# w65c265sxb_ym2149.net
KiCad netlist of a schematic drawn in EAGLE
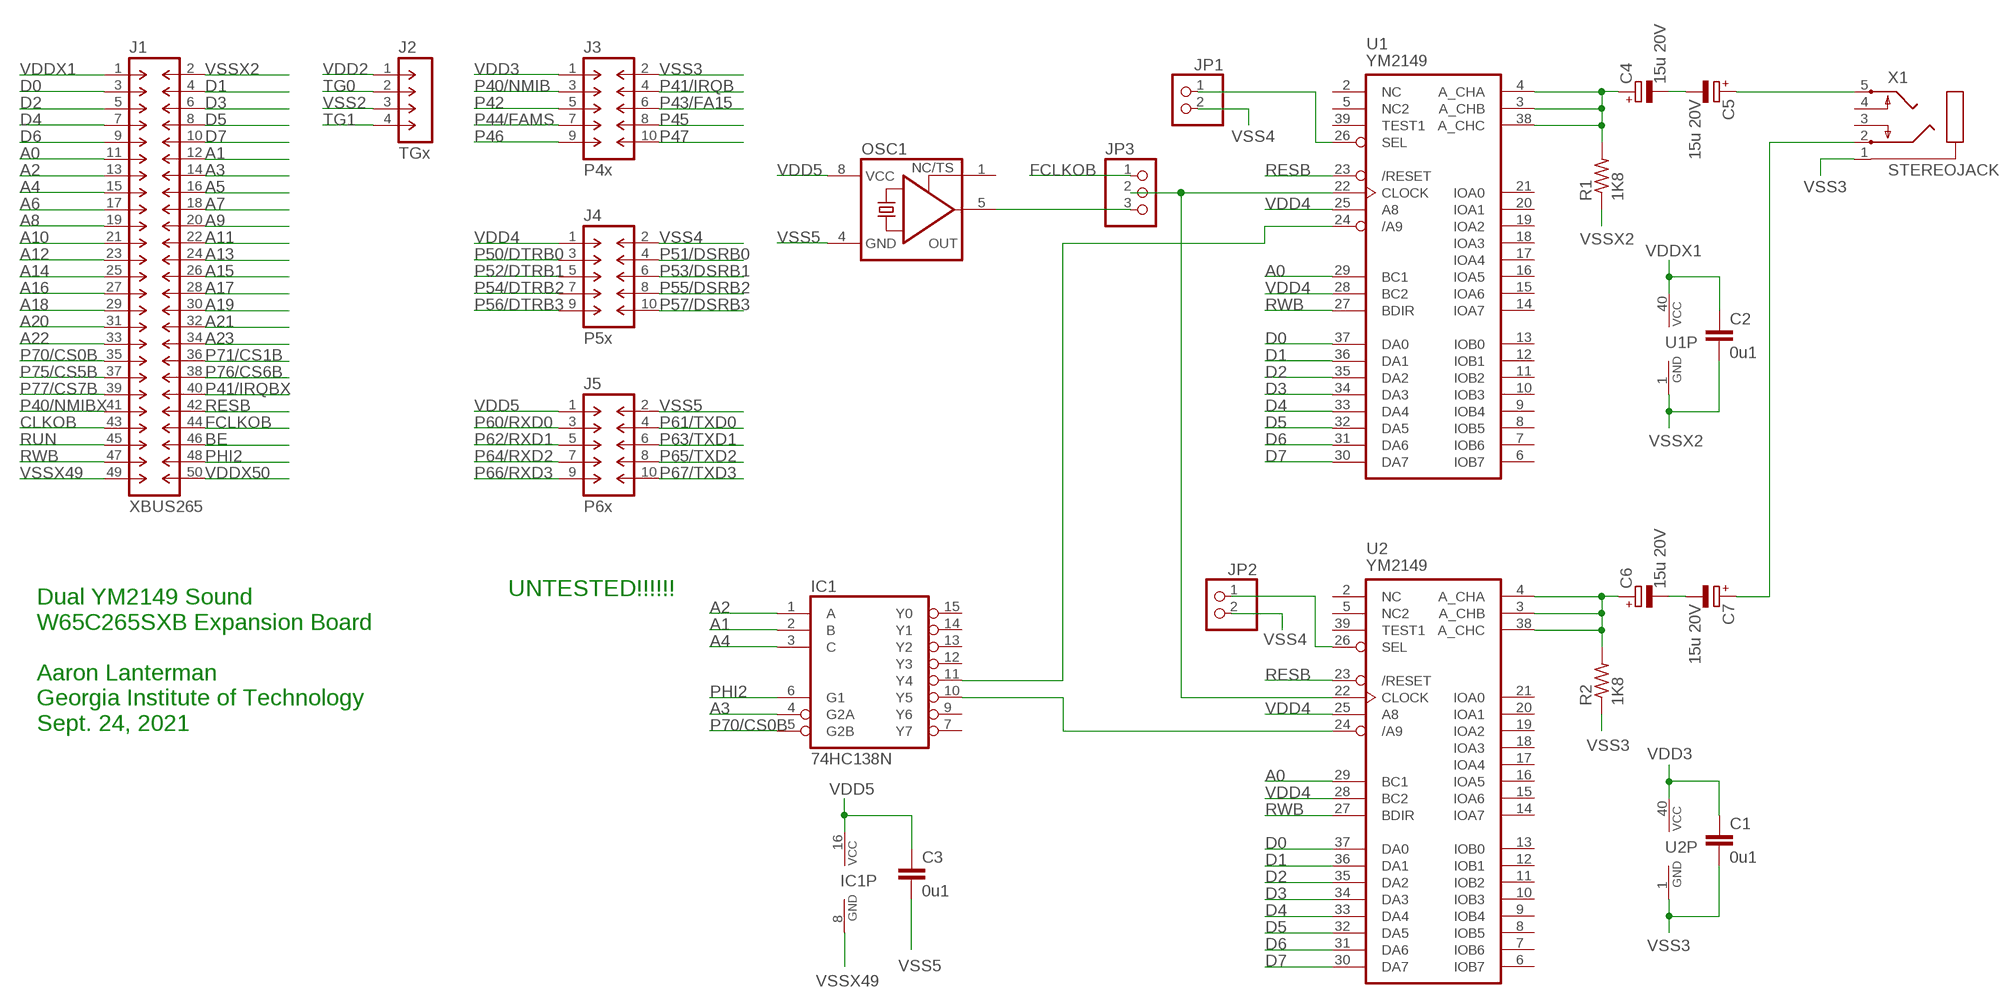
[diagram p0: schematic, sheet 1]

(export (version "E")
  (design (tool "Eeschema 10.0.6"))
  (components
    (comp (ref "C1")
      (value "0u1")
      (footprint "eagle-import:C050-025X075-AARON")
      (libsource (lib "eagle-import") (part "C-EU050-025X075-AARON"))
    )
    (comp (ref "C2")
      (value "0u1")
      (footprint "eagle-import:C050-025X075-AARON")
      (libsource (lib "eagle-import") (part "C-EU050-025X075-AARON"))
    )
    (comp (ref "C3")
      (value "0u1")
      (footprint "eagle-import:C050-025X075-AARON")
      (libsource (lib "eagle-import") (part "C-EU050-025X075-AARON"))
    )
    (comp (ref "C4")
      (value "15u 20V")
      (footprint "eagle-import:E2,5-7")
      (libsource (lib "eagle-import") (part "CPOL-EUE2.5-7"))
    )
    (comp (ref "C5")
      (value "15u 20V")
      (footprint "eagle-import:E2,5-7")
      (libsource (lib "eagle-import") (part "CPOL-EUE2.5-7"))
    )
    (comp (ref "C6")
      (value "15u 20V")
      (footprint "eagle-import:E2,5-7")
      (libsource (lib "eagle-import") (part "CPOL-EUE2.5-7"))
    )
    (comp (ref "C7")
      (value "15u 20V")
      (footprint "eagle-import:E2,5-7")
      (libsource (lib "eagle-import") (part "CPOL-EUE2.5-7"))
    )
    (comp (ref "IC1")
      (value "74HC138N")
      (footprint "eagle-import:DIL16")
      (libsource (lib "eagle-import") (part "74138NHC"))
    )
    (comp (ref "J1")
      (value "XBUS265")
      (footprint "eagle-import:DIL-100-2X25")
      (libsource (lib "eagle-import") (part "M-2X25-DIL-100"))
    )
    (comp (ref "J2")
      (value "TGx")
      (footprint "eagle-import:SIP-100-04-40")
      (libsource (lib "eagle-import") (part "M-1X04-SIP-100-40"))
    )
    (comp (ref "J3")
      (value "P4x")
      (footprint "eagle-import:DIL-100-2X05")
      (libsource (lib "eagle-import") (part "M-2X05-DIL-100"))
    )
    (comp (ref "J4")
      (value "P5x")
      (footprint "eagle-import:DIL-100-2X05")
      (libsource (lib "eagle-import") (part "M-2X05-DIL-100"))
    )
    (comp (ref "J5")
      (value "P6x")
      (footprint "eagle-import:DIL-100-2X05")
      (libsource (lib "eagle-import") (part "M-2X05-DIL-100"))
    )
    (comp (ref "JP1")
      (value "PINHD-1X2")
      (footprint "eagle-import:1X02")
      (libsource (lib "eagle-import") (part "PINHD-1X2"))
    )
    (comp (ref "JP2")
      (value "PINHD-1X2")
      (footprint "eagle-import:1X02")
      (libsource (lib "eagle-import") (part "PINHD-1X2"))
    )
    (comp (ref "JP3")
      (value "PINHD-1X3")
      (footprint "eagle-import:1X03")
      (libsource (lib "eagle-import") (part "PINHD-1X3"))
    )
    (comp (ref "OSC1")
      (value "XO-8")
      (footprint "eagle-import:DIL08S")
      (libsource (lib "eagle-import") (part "XO-8"))
    )
    (comp (ref "R1")
      (value "1K8")
      (footprint "eagle-import:0207_10")
      (libsource (lib "eagle-import") (part "R-US_0207/10"))
    )
    (comp (ref "R2")
      (value "1K8")
      (footprint "eagle-import:0207_10")
      (libsource (lib "eagle-import") (part "R-US_0207/10"))
    )
    (comp (ref "U1")
      (value "YM2149")
      (footprint "eagle-import:DIL40")
      (libsource (lib "eagle-import") (part "YM2149"))
    )
    (comp (ref "U2")
      (value "YM2149")
      (footprint "eagle-import:DIL40")
      (libsource (lib "eagle-import") (part "YM2149"))
    )
    (comp (ref "X1")
      (value "STEREOJACK")
      (footprint "eagle-import:STX3100")
      (libsource (lib "eagle-import") (part "STEREOJACK"))
    )
  )
  (nets
    (net (code "1") (name "/A0") (class "Default")
      (node (ref "J1") (pin "11") (pinfunction "11_11") (pintype "passive"))
      (node (ref "U1") (pin "29") (pinfunction "BC1_29") (pintype "input"))
      (node (ref "U2") (pin "29") (pinfunction "BC1_29") (pintype "input"))
    )
    (net (code "2") (name "/A1") (class "Default")
      (node (ref "IC1") (pin "2") (pinfunction "B_2") (pintype "input"))
      (node (ref "J1") (pin "12") (pinfunction "12_12") (pintype "passive"))
    )
    (net (code "3") (name "/A2") (class "Default")
      (node (ref "IC1") (pin "1") (pinfunction "A_1") (pintype "input"))
      (node (ref "J1") (pin "13") (pinfunction "13_13") (pintype "passive"))
    )
    (net (code "4") (name "/A3") (class "Default")
      (node (ref "IC1") (pin "4") (pinfunction "G2A_4") (pintype "input"))
      (node (ref "J1") (pin "14") (pinfunction "14_14") (pintype "passive"))
    )
    (net (code "5") (name "/A4") (class "Default")
      (node (ref "IC1") (pin "3") (pinfunction "C_3") (pintype "input"))
      (node (ref "J1") (pin "15") (pinfunction "15_15") (pintype "passive"))
    )
    (net (code "6") (name "/A5") (class "Default")
      (node (ref "J1") (pin "16") (pinfunction "16_16") (pintype "passive"))
    )
    (net (code "7") (name "/A6") (class "Default")
      (node (ref "J1") (pin "17") (pinfunction "17_17") (pintype "passive"))
    )
    (net (code "8") (name "/A7") (class "Default")
      (node (ref "J1") (pin "18") (pinfunction "18_18") (pintype "passive"))
    )
    (net (code "9") (name "/A8") (class "Default")
      (node (ref "J1") (pin "19") (pinfunction "19_19") (pintype "passive"))
    )
    (net (code "10") (name "/A9") (class "Default")
      (node (ref "J1") (pin "20") (pinfunction "20_20") (pintype "passive"))
    )
    (net (code "11") (name "/A10") (class "Default")
      (node (ref "J1") (pin "21") (pinfunction "21_21") (pintype "passive"))
    )
    (net (code "12") (name "/A11") (class "Default")
      (node (ref "J1") (pin "22") (pinfunction "22_22") (pintype "passive"))
    )
    (net (code "13") (name "/A12") (class "Default")
      (node (ref "J1") (pin "23") (pinfunction "23_23") (pintype "passive"))
    )
    (net (code "14") (name "/A13") (class "Default")
      (node (ref "J1") (pin "24") (pinfunction "24_24") (pintype "passive"))
    )
    (net (code "15") (name "/A14") (class "Default")
      (node (ref "J1") (pin "25") (pinfunction "25_25") (pintype "passive"))
    )
    (net (code "16") (name "/A15") (class "Default")
      (node (ref "J1") (pin "26") (pinfunction "26_26") (pintype "passive"))
    )
    (net (code "17") (name "/A16") (class "Default")
      (node (ref "J1") (pin "27") (pinfunction "27_27") (pintype "passive"))
    )
    (net (code "18") (name "/A17") (class "Default")
      (node (ref "J1") (pin "28") (pinfunction "28_28") (pintype "passive"))
    )
    (net (code "19") (name "/A18") (class "Default")
      (node (ref "J1") (pin "29") (pinfunction "29_29") (pintype "passive"))
    )
    (net (code "20") (name "/A19") (class "Default")
      (node (ref "J1") (pin "30") (pinfunction "30_30") (pintype "passive"))
    )
    (net (code "21") (name "/A20") (class "Default")
      (node (ref "J1") (pin "31") (pinfunction "31_31") (pintype "passive"))
    )
    (net (code "22") (name "/A21") (class "Default")
      (node (ref "J1") (pin "32") (pinfunction "32_32") (pintype "passive"))
    )
    (net (code "23") (name "/A22") (class "Default")
      (node (ref "J1") (pin "33") (pinfunction "33_33") (pintype "passive"))
    )
    (net (code "24") (name "/A23") (class "Default")
      (node (ref "J1") (pin "34") (pinfunction "34_34") (pintype "passive"))
    )
    (net (code "25") (name "/BE") (class "Default")
      (node (ref "J1") (pin "46") (pinfunction "46_46") (pintype "passive"))
    )
    (net (code "26") (name "/CLKOB") (class "Default")
      (node (ref "J1") (pin "43") (pinfunction "43_43") (pintype "passive"))
    )
    (net (code "27") (name "/D0") (class "Default")
      (node (ref "J1") (pin "3") (pinfunction "3_3") (pintype "passive"))
      (node (ref "U1") (pin "37") (pinfunction "DA0_37") (pintype "bidirectional"))
      (node (ref "U2") (pin "37") (pinfunction "DA0_37") (pintype "bidirectional"))
    )
    (net (code "28") (name "/D1") (class "Default")
      (node (ref "J1") (pin "4") (pinfunction "4_4") (pintype "passive"))
      (node (ref "U1") (pin "36") (pinfunction "DA1_36") (pintype "bidirectional"))
      (node (ref "U2") (pin "36") (pinfunction "DA1_36") (pintype "bidirectional"))
    )
    (net (code "29") (name "/D2") (class "Default")
      (node (ref "J1") (pin "5") (pinfunction "5_5") (pintype "passive"))
      (node (ref "U1") (pin "35") (pinfunction "DA2_35") (pintype "bidirectional"))
      (node (ref "U2") (pin "35") (pinfunction "DA2_35") (pintype "bidirectional"))
    )
    (net (code "30") (name "/D3") (class "Default")
      (node (ref "J1") (pin "6") (pinfunction "6_6") (pintype "passive"))
      (node (ref "U1") (pin "34") (pinfunction "DA3_34") (pintype "bidirectional"))
      (node (ref "U2") (pin "34") (pinfunction "DA3_34") (pintype "bidirectional"))
    )
    (net (code "31") (name "/D4") (class "Default")
      (node (ref "J1") (pin "7") (pinfunction "7_7") (pintype "passive"))
      (node (ref "U1") (pin "33") (pinfunction "DA4_33") (pintype "bidirectional"))
      (node (ref "U2") (pin "33") (pinfunction "DA4_33") (pintype "bidirectional"))
    )
    (net (code "32") (name "/D5") (class "Default")
      (node (ref "J1") (pin "8") (pinfunction "8_8") (pintype "passive"))
      (node (ref "U1") (pin "32") (pinfunction "DA5_32") (pintype "bidirectional"))
      (node (ref "U2") (pin "32") (pinfunction "DA5_32") (pintype "bidirectional"))
    )
    (net (code "33") (name "/D6") (class "Default")
      (node (ref "J1") (pin "9") (pinfunction "9_9") (pintype "passive"))
      (node (ref "U1") (pin "31") (pinfunction "DA6_31") (pintype "bidirectional"))
      (node (ref "U2") (pin "31") (pinfunction "DA6_31") (pintype "bidirectional"))
    )
    (net (code "34") (name "/D7") (class "Default")
      (node (ref "J1") (pin "10") (pinfunction "10_10") (pintype "passive"))
      (node (ref "U1") (pin "30") (pinfunction "DA7_30") (pintype "bidirectional"))
      (node (ref "U2") (pin "30") (pinfunction "DA7_30") (pintype "bidirectional"))
    )
    (net (code "35") (name "/FCLKOB") (class "Default")
      (node (ref "J1") (pin "44") (pinfunction "44_44") (pintype "passive"))
      (node (ref "JP3") (pin "1") (pinfunction "1_1") (pintype "passive"))
    )
    (net (code "36") (name "/P40{slash}NMIB") (class "Default")
      (node (ref "J3") (pin "3") (pinfunction "3_3") (pintype "passive"))
    )
    (net (code "37") (name "/P40{slash}NMIBX") (class "Default")
      (node (ref "J1") (pin "41") (pinfunction "41_41") (pintype "passive"))
    )
    (net (code "38") (name "/P41{slash}IRQB") (class "Default")
      (node (ref "J3") (pin "4") (pinfunction "4_4") (pintype "passive"))
    )
    (net (code "39") (name "/P41{slash}IRQBX") (class "Default")
      (node (ref "J1") (pin "40") (pinfunction "40_40") (pintype "passive"))
    )
    (net (code "40") (name "/P42") (class "Default")
      (node (ref "J3") (pin "5") (pinfunction "5_5") (pintype "passive"))
    )
    (net (code "41") (name "/P43{slash}FA15") (class "Default")
      (node (ref "J3") (pin "6") (pinfunction "6_6") (pintype "passive"))
    )
    (net (code "42") (name "/P44{slash}FAMS") (class "Default")
      (node (ref "J3") (pin "7") (pinfunction "7_7") (pintype "passive"))
    )
    (net (code "43") (name "/P45") (class "Default")
      (node (ref "J3") (pin "8") (pinfunction "8_8") (pintype "passive"))
    )
    (net (code "44") (name "/P46") (class "Default")
      (node (ref "J3") (pin "9") (pinfunction "9_9") (pintype "passive"))
    )
    (net (code "45") (name "/P47") (class "Default")
      (node (ref "J3") (pin "10") (pinfunction "10_10") (pintype "passive"))
    )
    (net (code "46") (name "/P50{slash}DTRB0") (class "Default")
      (node (ref "J4") (pin "3") (pinfunction "3_3") (pintype "passive"))
    )
    (net (code "47") (name "/P51{slash}DSRB0") (class "Default")
      (node (ref "J4") (pin "4") (pinfunction "4_4") (pintype "passive"))
    )
    (net (code "48") (name "/P52{slash}DTRB1") (class "Default")
      (node (ref "J4") (pin "5") (pinfunction "5_5") (pintype "passive"))
    )
    (net (code "49") (name "/P53{slash}DSRB1") (class "Default")
      (node (ref "J4") (pin "6") (pinfunction "6_6") (pintype "passive"))
    )
    (net (code "50") (name "/P54{slash}DTRB2") (class "Default")
      (node (ref "J4") (pin "7") (pinfunction "7_7") (pintype "passive"))
    )
    (net (code "51") (name "/P55{slash}DSRB2") (class "Default")
      (node (ref "J4") (pin "8") (pinfunction "8_8") (pintype "passive"))
    )
    (net (code "52") (name "/P56{slash}DTRB3") (class "Default")
      (node (ref "J4") (pin "9") (pinfunction "9_9") (pintype "passive"))
    )
    (net (code "53") (name "/P57{slash}DSRB3") (class "Default")
      (node (ref "J4") (pin "10") (pinfunction "10_10") (pintype "passive"))
    )
    (net (code "54") (name "/P60{slash}RXD0") (class "Default")
      (node (ref "J5") (pin "3") (pinfunction "3_3") (pintype "passive"))
    )
    (net (code "55") (name "/P61{slash}TXD0") (class "Default")
      (node (ref "J5") (pin "4") (pinfunction "4_4") (pintype "passive"))
    )
    (net (code "56") (name "/P62{slash}RXD1") (class "Default")
      (node (ref "J5") (pin "5") (pinfunction "5_5") (pintype "passive"))
    )
    (net (code "57") (name "/P63{slash}TXD1") (class "Default")
      (node (ref "J5") (pin "6") (pinfunction "6_6") (pintype "passive"))
    )
    (net (code "58") (name "/P64{slash}RXD2") (class "Default")
      (node (ref "J5") (pin "7") (pinfunction "7_7") (pintype "passive"))
    )
    (net (code "59") (name "/P65{slash}TXD2") (class "Default")
      (node (ref "J5") (pin "8") (pinfunction "8_8") (pintype "passive"))
    )
    (net (code "60") (name "/P66{slash}RXD3") (class "Default")
      (node (ref "J5") (pin "9") (pinfunction "9_9") (pintype "passive"))
    )
    (net (code "61") (name "/P67{slash}TXD3") (class "Default")
      (node (ref "J5") (pin "10") (pinfunction "10_10") (pintype "passive"))
    )
    (net (code "62") (name "/P70{slash}CS0B") (class "Default")
      (node (ref "IC1") (pin "5") (pinfunction "G2B_5") (pintype "input"))
      (node (ref "J1") (pin "35") (pinfunction "35_35") (pintype "passive"))
    )
    (net (code "63") (name "/P71{slash}CS1B") (class "Default")
      (node (ref "J1") (pin "36") (pinfunction "36_36") (pintype "passive"))
    )
    (net (code "64") (name "/P75{slash}CS5B") (class "Default")
      (node (ref "J1") (pin "37") (pinfunction "37_37") (pintype "passive"))
    )
    (net (code "65") (name "/P76{slash}CS6B") (class "Default")
      (node (ref "J1") (pin "38") (pinfunction "38_38") (pintype "passive"))
    )
    (net (code "66") (name "/P77{slash}CS7B") (class "Default")
      (node (ref "J1") (pin "39") (pinfunction "39_39") (pintype "passive"))
    )
    (net (code "67") (name "/PHI2") (class "Default")
      (node (ref "IC1") (pin "6") (pinfunction "G1_6") (pintype "input"))
      (node (ref "J1") (pin "48") (pinfunction "48_48") (pintype "passive"))
    )
    (net (code "68") (name "/RESB") (class "Default")
      (node (ref "J1") (pin "42") (pinfunction "42_42") (pintype "passive"))
      (node (ref "U1") (pin "23") (pinfunction "/RESET_23") (pintype "input"))
      (node (ref "U2") (pin "23") (pinfunction "/RESET_23") (pintype "input"))
    )
    (net (code "69") (name "/RUN") (class "Default")
      (node (ref "J1") (pin "45") (pinfunction "45_45") (pintype "passive"))
    )
    (net (code "70") (name "/RWB") (class "Default")
      (node (ref "J1") (pin "47") (pinfunction "47_47") (pintype "passive"))
      (node (ref "U1") (pin "27") (pinfunction "BDIR_27") (pintype "input"))
      (node (ref "U2") (pin "27") (pinfunction "BDIR_27") (pintype "input"))
    )
    (net (code "71") (name "/TG0") (class "Default")
      (node (ref "J2") (pin "2") (pinfunction "2_2") (pintype "passive"))
    )
    (net (code "72") (name "/TG1") (class "Default")
      (node (ref "J2") (pin "4") (pinfunction "4_4") (pintype "passive"))
    )
    (net (code "73") (name "/VDD2") (class "Default")
      (node (ref "J2") (pin "1") (pinfunction "1_1") (pintype "passive"))
    )
    (net (code "74") (name "/VDD3") (class "Default")
      (node (ref "C1") (pin "1") (pinfunction "1_1") (pintype "passive"))
      (node (ref "J3") (pin "1") (pinfunction "1_1") (pintype "passive"))
      (node (ref "U2") (pin "40") (pinfunction "VCC_40") (pintype "power_in"))
    )
    (net (code "75") (name "/VDD4") (class "Default")
      (node (ref "J4") (pin "1") (pinfunction "1_1") (pintype "passive"))
      (node (ref "U1") (pin "25") (pinfunction "A8_25") (pintype "input"))
      (node (ref "U1") (pin "28") (pinfunction "BC2_28") (pintype "input"))
      (node (ref "U2") (pin "25") (pinfunction "A8_25") (pintype "input"))
      (node (ref "U2") (pin "28") (pinfunction "BC2_28") (pintype "input"))
    )
    (net (code "76") (name "/VDD5") (class "Default")
      (node (ref "C3") (pin "1") (pinfunction "1_1") (pintype "passive"))
      (node (ref "IC1") (pin "16") (pinfunction "VCC_16") (pintype "power_in"))
      (node (ref "J5") (pin "1") (pinfunction "1_1") (pintype "passive"))
      (node (ref "OSC1") (pin "8") (pinfunction "VCC_8") (pintype "power_in"))
    )
    (net (code "77") (name "/VDDX1") (class "Default")
      (node (ref "C2") (pin "1") (pinfunction "1_1") (pintype "passive"))
      (node (ref "J1") (pin "1") (pinfunction "1_1") (pintype "passive"))
      (node (ref "U1") (pin "40") (pinfunction "VCC_40") (pintype "power_in"))
    )
    (net (code "78") (name "/VDDX50") (class "Default")
      (node (ref "J1") (pin "50") (pinfunction "50_50") (pintype "passive"))
    )
    (net (code "79") (name "/VSS2") (class "Default")
      (node (ref "J2") (pin "3") (pinfunction "3_3") (pintype "passive"))
    )
    (net (code "80") (name "/VSS3") (class "Default")
      (node (ref "C1") (pin "2") (pinfunction "2_2") (pintype "passive"))
      (node (ref "J3") (pin "2") (pinfunction "2_2") (pintype "passive"))
      (node (ref "R2") (pin "1") (pinfunction "1_1") (pintype "passive"))
      (node (ref "U2") (pin "1") (pinfunction "GND_1") (pintype "power_in"))
      (node (ref "X1") (pin "1") (pinfunction "1_1") (pintype "passive"))
    )
    (net (code "81") (name "/VSS4") (class "Default")
      (node (ref "J4") (pin "2") (pinfunction "2_2") (pintype "passive"))
      (node (ref "JP1") (pin "2") (pinfunction "2_2") (pintype "passive"))
      (node (ref "JP2") (pin "2") (pinfunction "2_2") (pintype "passive"))
    )
    (net (code "82") (name "/VSS5") (class "Default")
      (node (ref "C3") (pin "2") (pinfunction "2_2") (pintype "passive"))
      (node (ref "J5") (pin "2") (pinfunction "2_2") (pintype "passive"))
      (node (ref "OSC1") (pin "4") (pinfunction "GND_4") (pintype "power_in"))
    )
    (net (code "83") (name "/VSSX2") (class "Default")
      (node (ref "C2") (pin "2") (pinfunction "2_2") (pintype "passive"))
      (node (ref "J1") (pin "2") (pinfunction "2_2") (pintype "passive"))
      (node (ref "R1") (pin "1") (pinfunction "1_1") (pintype "passive"))
      (node (ref "U1") (pin "1") (pinfunction "GND_1") (pintype "power_in"))
    )
    (net (code "84") (name "/VSSX49") (class "Default")
      (node (ref "IC1") (pin "8") (pinfunction "GND_8") (pintype "power_in"))
      (node (ref "J1") (pin "49") (pinfunction "49_49") (pintype "passive"))
    )
    (net (code "85") (name "Net-(C4-Pad-)") (class "Default")
      (node (ref "C4") (pin "-") (pinfunction "-_-") (pintype "passive"))
      (node (ref "C5") (pin "-") (pinfunction "-_-") (pintype "passive"))
    )
    (net (code "86") (name "Net-(C5-Pad+)") (class "Default")
      (node (ref "C5") (pin "+") (pinfunction "+_+") (pintype "passive"))
      (node (ref "X1") (pin "5") (pinfunction "5_5") (pintype "passive"))
    )
    (net (code "87") (name "Net-(C6-Pad-)") (class "Default")
      (node (ref "C6") (pin "-") (pinfunction "-_-") (pintype "passive"))
      (node (ref "C7") (pin "-") (pinfunction "-_-") (pintype "passive"))
    )
    (net (code "88") (name "Net-(C7-Pad+)") (class "Default")
      (node (ref "C7") (pin "+") (pinfunction "+_+") (pintype "passive"))
      (node (ref "X1") (pin "2") (pinfunction "2_2") (pintype "passive"))
    )
    (net (code "89") (name "Net-(IC1A-Y4)") (class "Default")
      (node (ref "IC1") (pin "11") (pinfunction "Y4_11") (pintype "output"))
      (node (ref "U1") (pin "24") (pinfunction "/A9_24") (pintype "input"))
    )
    (net (code "90") (name "Net-(IC1A-Y5)") (class "Default")
      (node (ref "IC1") (pin "10") (pinfunction "Y5_10") (pintype "output"))
      (node (ref "U2") (pin "24") (pinfunction "/A9_24") (pintype "input"))
    )
    (net (code "91") (name "Net-(OSC1-OUT)") (class "Default")
      (node (ref "JP3") (pin "3") (pinfunction "3_3") (pintype "passive"))
      (node (ref "OSC1") (pin "5") (pinfunction "OUT_5") (pintype "output"))
    )
    (net (code "92") (name "Net-(U1A-A_CHA)") (class "Default")
      (node (ref "C4") (pin "+") (pinfunction "+_+") (pintype "passive"))
      (node (ref "R1") (pin "2") (pinfunction "2_2") (pintype "passive"))
      (node (ref "U1") (pin "3") (pinfunction "A_CHB_3") (pintype "output"))
      (node (ref "U1") (pin "38") (pinfunction "A_CHC_38") (pintype "output"))
      (node (ref "U1") (pin "4") (pinfunction "A_CHA_4") (pintype "output"))
    )
    (net (code "93") (name "Net-(U1A-CLOCK)") (class "Default")
      (node (ref "JP3") (pin "2") (pinfunction "2_2") (pintype "passive"))
      (node (ref "U1") (pin "22") (pinfunction "CLOCK_22") (pintype "input"))
      (node (ref "U2") (pin "22") (pinfunction "CLOCK_22") (pintype "input"))
    )
    (net (code "94") (name "Net-(U1A-SEL)") (class "Default")
      (node (ref "JP1") (pin "1") (pinfunction "1_1") (pintype "passive"))
      (node (ref "U1") (pin "26") (pinfunction "SEL_26") (pintype "input"))
    )
    (net (code "95") (name "Net-(U2A-A_CHA)") (class "Default")
      (node (ref "C6") (pin "+") (pinfunction "+_+") (pintype "passive"))
      (node (ref "R2") (pin "2") (pinfunction "2_2") (pintype "passive"))
      (node (ref "U2") (pin "3") (pinfunction "A_CHB_3") (pintype "output"))
      (node (ref "U2") (pin "38") (pinfunction "A_CHC_38") (pintype "output"))
      (node (ref "U2") (pin "4") (pinfunction "A_CHA_4") (pintype "output"))
    )
    (net (code "96") (name "Net-(U2A-SEL)") (class "Default")
      (node (ref "JP2") (pin "1") (pinfunction "1_1") (pintype "passive"))
      (node (ref "U2") (pin "26") (pinfunction "SEL_26") (pintype "input"))
    )
    (net (code "97") (name "unconnected-(IC1A-Y0-Pad15)") (class "Default")
      (node (ref "IC1") (pin "15") (pinfunction "Y0_15") (pintype "output"))
    )
    (net (code "98") (name "unconnected-(IC1A-Y1-Pad14)") (class "Default")
      (node (ref "IC1") (pin "14") (pinfunction "Y1_14") (pintype "output"))
    )
    (net (code "99") (name "unconnected-(IC1A-Y2-Pad13)") (class "Default")
      (node (ref "IC1") (pin "13") (pinfunction "Y2_13") (pintype "output"))
    )
    (net (code "100") (name "unconnected-(IC1A-Y3-Pad12)") (class "Default")
      (node (ref "IC1") (pin "12") (pinfunction "Y3_12") (pintype "output"))
    )
    (net (code "101") (name "unconnected-(IC1A-Y6-Pad9)") (class "Default")
      (node (ref "IC1") (pin "9") (pinfunction "Y6_9") (pintype "output"))
    )
    (net (code "102") (name "unconnected-(IC1A-Y7-Pad7)") (class "Default")
      (node (ref "IC1") (pin "7") (pinfunction "Y7_7") (pintype "output"))
    )
    (net (code "103") (name "unconnected-(OSC1-TS-Pad1)") (class "Default")
      (node (ref "OSC1") (pin "1") (pinfunction "TS_1") (pintype "passive"))
    )
    (net (code "104") (name "unconnected-(U1A-IOA0-Pad21)") (class "Default")
      (node (ref "U1") (pin "21") (pinfunction "IOA0_21") (pintype "bidirectional"))
    )
    (net (code "105") (name "unconnected-(U1A-IOA1-Pad20)") (class "Default")
      (node (ref "U1") (pin "20") (pinfunction "IOA1_20") (pintype "bidirectional"))
    )
    (net (code "106") (name "unconnected-(U1A-IOA2-Pad19)") (class "Default")
      (node (ref "U1") (pin "19") (pinfunction "IOA2_19") (pintype "bidirectional"))
    )
    (net (code "107") (name "unconnected-(U1A-IOA3-Pad18)") (class "Default")
      (node (ref "U1") (pin "18") (pinfunction "IOA3_18") (pintype "bidirectional"))
    )
    (net (code "108") (name "unconnected-(U1A-IOA4-Pad17)") (class "Default")
      (node (ref "U1") (pin "17") (pinfunction "IOA4_17") (pintype "bidirectional"))
    )
    (net (code "109") (name "unconnected-(U1A-IOA5-Pad16)") (class "Default")
      (node (ref "U1") (pin "16") (pinfunction "IOA5_16") (pintype "bidirectional"))
    )
    (net (code "110") (name "unconnected-(U1A-IOA6-Pad15)") (class "Default")
      (node (ref "U1") (pin "15") (pinfunction "IOA6_15") (pintype "bidirectional"))
    )
    (net (code "111") (name "unconnected-(U1A-IOA7-Pad14)") (class "Default")
      (node (ref "U1") (pin "14") (pinfunction "IOA7_14") (pintype "bidirectional"))
    )
    (net (code "112") (name "unconnected-(U1A-IOB0-Pad13)") (class "Default")
      (node (ref "U1") (pin "13") (pinfunction "IOB0_13") (pintype "bidirectional"))
    )
    (net (code "113") (name "unconnected-(U1A-IOB1-Pad12)") (class "Default")
      (node (ref "U1") (pin "12") (pinfunction "IOB1_12") (pintype "bidirectional"))
    )
    (net (code "114") (name "unconnected-(U1A-IOB2-Pad11)") (class "Default")
      (node (ref "U1") (pin "11") (pinfunction "IOB2_11") (pintype "bidirectional"))
    )
    (net (code "115") (name "unconnected-(U1A-IOB3-Pad10)") (class "Default")
      (node (ref "U1") (pin "10") (pinfunction "IOB3_10") (pintype "bidirectional"))
    )
    (net (code "116") (name "unconnected-(U1A-IOB4-Pad9)") (class "Default")
      (node (ref "U1") (pin "9") (pinfunction "IOB4_9") (pintype "bidirectional"))
    )
    (net (code "117") (name "unconnected-(U1A-IOB5-Pad8)") (class "Default")
      (node (ref "U1") (pin "8") (pinfunction "IOB5_8") (pintype "bidirectional"))
    )
    (net (code "118") (name "unconnected-(U1A-IOB6-Pad7)") (class "Default")
      (node (ref "U1") (pin "7") (pinfunction "IOB6_7") (pintype "bidirectional"))
    )
    (net (code "119") (name "unconnected-(U1A-IOB7-Pad6)") (class "Default")
      (node (ref "U1") (pin "6") (pinfunction "IOB7_6") (pintype "bidirectional"))
    )
    (net (code "120") (name "unconnected-(U1A-NC-Pad2)") (class "Default")
      (node (ref "U1") (pin "2") (pinfunction "NC_2") (pintype "no_connect"))
    )
    (net (code "121") (name "unconnected-(U1A-NC2-Pad5)") (class "Default")
      (node (ref "U1") (pin "5") (pinfunction "NC2_5") (pintype "no_connect"))
    )
    (net (code "122") (name "unconnected-(U1A-TEST1-Pad39)") (class "Default")
      (node (ref "U1") (pin "39") (pinfunction "TEST1_39") (pintype "input"))
    )
    (net (code "123") (name "unconnected-(U2A-IOA0-Pad21)") (class "Default")
      (node (ref "U2") (pin "21") (pinfunction "IOA0_21") (pintype "bidirectional"))
    )
    (net (code "124") (name "unconnected-(U2A-IOA1-Pad20)") (class "Default")
      (node (ref "U2") (pin "20") (pinfunction "IOA1_20") (pintype "bidirectional"))
    )
    (net (code "125") (name "unconnected-(U2A-IOA2-Pad19)") (class "Default")
      (node (ref "U2") (pin "19") (pinfunction "IOA2_19") (pintype "bidirectional"))
    )
    (net (code "126") (name "unconnected-(U2A-IOA3-Pad18)") (class "Default")
      (node (ref "U2") (pin "18") (pinfunction "IOA3_18") (pintype "bidirectional"))
    )
    (net (code "127") (name "unconnected-(U2A-IOA4-Pad17)") (class "Default")
      (node (ref "U2") (pin "17") (pinfunction "IOA4_17") (pintype "bidirectional"))
    )
    (net (code "128") (name "unconnected-(U2A-IOA5-Pad16)") (class "Default")
      (node (ref "U2") (pin "16") (pinfunction "IOA5_16") (pintype "bidirectional"))
    )
    (net (code "129") (name "unconnected-(U2A-IOA6-Pad15)") (class "Default")
      (node (ref "U2") (pin "15") (pinfunction "IOA6_15") (pintype "bidirectional"))
    )
    (net (code "130") (name "unconnected-(U2A-IOA7-Pad14)") (class "Default")
      (node (ref "U2") (pin "14") (pinfunction "IOA7_14") (pintype "bidirectional"))
    )
    (net (code "131") (name "unconnected-(U2A-IOB0-Pad13)") (class "Default")
      (node (ref "U2") (pin "13") (pinfunction "IOB0_13") (pintype "bidirectional"))
    )
    (net (code "132") (name "unconnected-(U2A-IOB1-Pad12)") (class "Default")
      (node (ref "U2") (pin "12") (pinfunction "IOB1_12") (pintype "bidirectional"))
    )
    (net (code "133") (name "unconnected-(U2A-IOB2-Pad11)") (class "Default")
      (node (ref "U2") (pin "11") (pinfunction "IOB2_11") (pintype "bidirectional"))
    )
    (net (code "134") (name "unconnected-(U2A-IOB3-Pad10)") (class "Default")
      (node (ref "U2") (pin "10") (pinfunction "IOB3_10") (pintype "bidirectional"))
    )
    (net (code "135") (name "unconnected-(U2A-IOB4-Pad9)") (class "Default")
      (node (ref "U2") (pin "9") (pinfunction "IOB4_9") (pintype "bidirectional"))
    )
    (net (code "136") (name "unconnected-(U2A-IOB5-Pad8)") (class "Default")
      (node (ref "U2") (pin "8") (pinfunction "IOB5_8") (pintype "bidirectional"))
    )
    (net (code "137") (name "unconnected-(U2A-IOB6-Pad7)") (class "Default")
      (node (ref "U2") (pin "7") (pinfunction "IOB6_7") (pintype "bidirectional"))
    )
    (net (code "138") (name "unconnected-(U2A-IOB7-Pad6)") (class "Default")
      (node (ref "U2") (pin "6") (pinfunction "IOB7_6") (pintype "bidirectional"))
    )
    (net (code "139") (name "unconnected-(U2A-NC-Pad2)") (class "Default")
      (node (ref "U2") (pin "2") (pinfunction "NC_2") (pintype "no_connect"))
    )
    (net (code "140") (name "unconnected-(U2A-NC2-Pad5)") (class "Default")
      (node (ref "U2") (pin "5") (pinfunction "NC2_5") (pintype "no_connect"))
    )
    (net (code "141") (name "unconnected-(U2A-TEST1-Pad39)") (class "Default")
      (node (ref "U2") (pin "39") (pinfunction "TEST1_39") (pintype "input"))
    )
    (net (code "142") (name "unconnected-(X1-Pad3)") (class "Default")
      (node (ref "X1") (pin "3") (pinfunction "3_3") (pintype "passive"))
    )
    (net (code "143") (name "unconnected-(X1-Pad4)") (class "Default")
      (node (ref "X1") (pin "4") (pinfunction "4_4") (pintype "passive"))
    )
  )
)
